# 1-Schematic_V1_0-A4988.net
KiCad netlist of a schematic drawn in EasyEDA
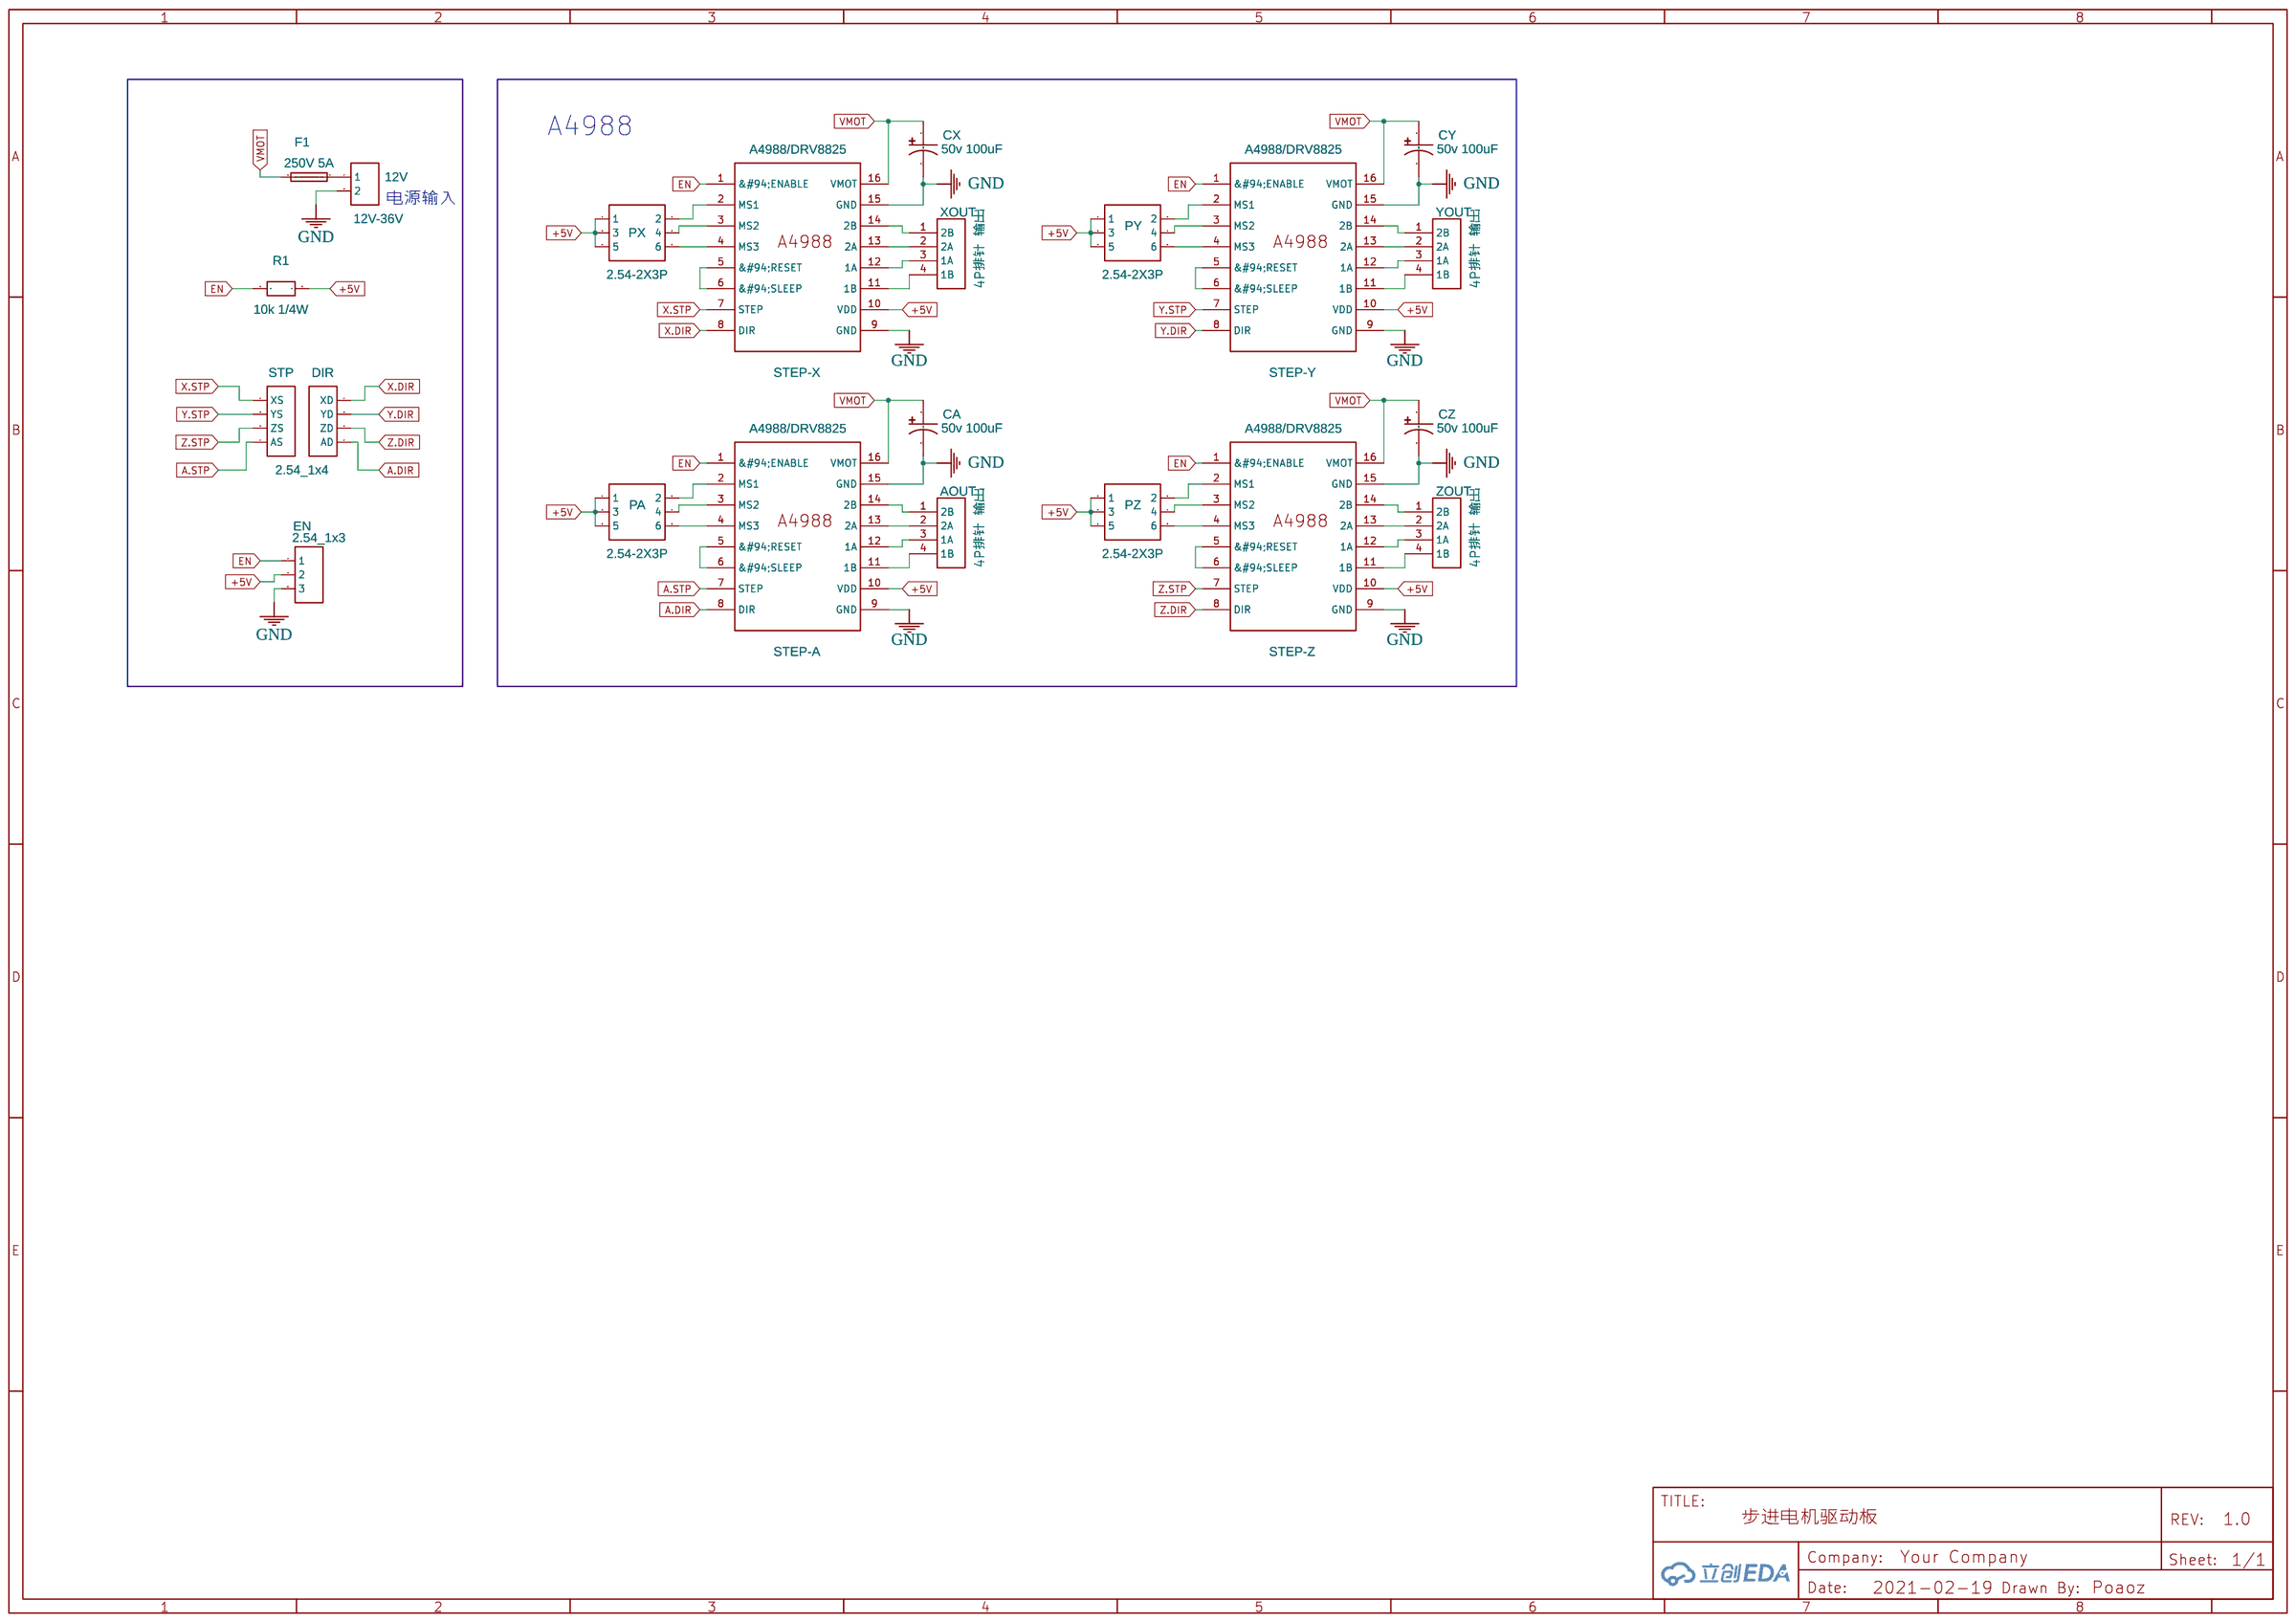
[diagram p0: schematic sheet]

(export (version "E")
  (design (tool "Eeschema 10.0.6"))
  (components
    (comp (ref "12V") (value "12V-36V") (libsource (lib "") (part "CONN-TH_2P-P5.00")))
    (comp (ref "AOUT") (value "4P排针 输出") (libsource (lib "") (part "4P排针_2")))
    (comp (ref "CA")
      (value "50v 100uF")
      (fields
        (field (name "BOM_Manufacturer Part") "NXA-50V100-8*11.5")
        (field (name "BOM_Supplier Part") "C165524")
      )
      (libsource (lib "") (part "NXA-50V100-8*11.5"))
    )
    (comp (ref "CX")
      (value "50v 100uF")
      (fields
        (field (name "BOM_Manufacturer Part") "NXA-50V100-8*11.5")
        (field (name "BOM_Supplier Part") "C165524")
      )
      (libsource (lib "") (part "NXA-50V100-8*11.5_2"))
    )
    (comp (ref "CY")
      (value "50v 100uF")
      (fields
        (field (name "BOM_Manufacturer Part") "NXA-50V100-8*11.5")
        (field (name "BOM_Supplier Part") "C165524")
      )
      (libsource (lib "") (part "NXA-50V100-8*11.5_1"))
    )
    (comp (ref "CZ")
      (value "50v 100uF")
      (fields
        (field (name "BOM_Manufacturer Part") "NXA-50V100-8*11.5")
        (field (name "BOM_Supplier Part") "C165524")
      )
      (libsource (lib "") (part "NXA-50V100-8*11.5_3"))
    )
    (comp (ref "DIR")
      (value "2.54_1x4")
      (fields (field (name "BOM_Supplier Part") "C225501"))
      (libsource (lib "") (part "HDR-F-2.54_1x4"))
    )
    (comp (ref "EN")
      (value "2.54_1x3")
      (fields (field (name "BOM_Supplier Part") "C146690"))
      (libsource (lib "") (part "HDR-F-2.54_1x3"))
    )
    (comp (ref "F1")
      (value "250V 5A")
      (fields
        (field (name "BOM_Manufacturer Part") "250V 5A Slow break")
        (field (name "BOM_Supplier Part") "C38454")
      )
      (libsource (lib "") (part "250V 5A Slow break"))
    )
    (comp (ref "PA")
      (value "2.54-2X3P")
      (fields
        (field (name "BOM_Manufacturer Part") "2X3 2.54mm IDC Box")
        (field (name "BOM_Supplier Part") "C11214")
      )
      (libsource (lib "") (part "HDR-IDC-2.54-2X3P_2"))
    )
    (comp (ref "PX")
      (value "2.54-2X3P")
      (fields
        (field (name "BOM_Manufacturer Part") "2X3 2.54mm IDC Box")
        (field (name "BOM_Supplier Part") "C11214")
      )
      (libsource (lib "") (part "HDR-IDC-2.54-2X3P_3"))
    )
    (comp (ref "PY")
      (value "2.54-2X3P")
      (fields
        (field (name "BOM_Manufacturer Part") "2X3 2.54mm IDC Box")
        (field (name "BOM_Supplier Part") "C11214")
      )
      (libsource (lib "") (part "HDR-IDC-2.54-2X3P_1"))
    )
    (comp (ref "PZ")
      (value "2.54-2X3P")
      (fields
        (field (name "BOM_Manufacturer Part") "2X3 2.54mm IDC Box")
        (field (name "BOM_Supplier Part") "C11214")
      )
      (libsource (lib "") (part "HDR-IDC-2.54-2X3P"))
    )
    (comp (ref "R1") (value "10k 1/4W") (libsource (lib "") (part "R_0603_EU")))
    (comp (ref "STEP-A") (value "A4988/DRV8825") (libsource (lib "") (part "A4988/DRV8825_2")))
    (comp (ref "STEP-X") (value "A4988/DRV8825") (libsource (lib "") (part "A4988/DRV8825")))
    (comp (ref "STEP-Y") (value "A4988/DRV8825") (libsource (lib "") (part "A4988/DRV8825_3")))
    (comp (ref "STEP-Z") (value "A4988/DRV8825") (libsource (lib "") (part "A4988/DRV8825_1")))
    (comp (ref "STP")
      (value "HDR-F-2.54_1x4")
      (fields (field (name "BOM_Supplier Part") "C225501"))
      (libsource (lib "") (part "HDR-F-2.54_1x4_1"))
    )
    (comp (ref "XOUT") (value "4P排针 输出") (libsource (lib "") (part "4P排针")))
    (comp (ref "YOUT") (value "4P排针 输出") (libsource (lib "") (part "4P排针_1")))
    (comp (ref "ZOUT") (value "4P排针 输出") (libsource (lib "") (part "4P排针_3")))
  )
  (nets
    (net (code "1") (name "+5V") (class "Default")
      (node (ref "EN") (pin "2") (pinfunction "2_2") (pintype "input"))
      (node (ref "PA") (pin "1") (pinfunction "1_1") (pintype "unspecified"))
      (node (ref "PA") (pin "3") (pinfunction "3_3") (pintype "unspecified"))
      (node (ref "PA") (pin "5") (pinfunction "5_5") (pintype "unspecified"))
      (node (ref "PX") (pin "1") (pinfunction "1_1") (pintype "unspecified"))
      (node (ref "PX") (pin "3") (pinfunction "3_3") (pintype "unspecified"))
      (node (ref "PX") (pin "5") (pinfunction "5_5") (pintype "unspecified"))
      (node (ref "PY") (pin "1") (pinfunction "1_1") (pintype "unspecified"))
      (node (ref "PY") (pin "3") (pinfunction "3_3") (pintype "unspecified"))
      (node (ref "PY") (pin "5") (pinfunction "5_5") (pintype "unspecified"))
      (node (ref "PZ") (pin "1") (pinfunction "1_1") (pintype "unspecified"))
      (node (ref "PZ") (pin "3") (pinfunction "3_3") (pintype "unspecified"))
      (node (ref "PZ") (pin "5") (pinfunction "5_5") (pintype "unspecified"))
      (node (ref "R1") (pin "2") (pinfunction "2_2") (pintype "unspecified"))
      (node (ref "STEP-A") (pin "10") (pinfunction "VDD_10") (pintype "unspecified"))
      (node (ref "STEP-X") (pin "10") (pinfunction "VDD_10") (pintype "unspecified"))
      (node (ref "STEP-Y") (pin "10") (pinfunction "VDD_10") (pintype "unspecified"))
      (node (ref "STEP-Z") (pin "10") (pinfunction "VDD_10") (pintype "unspecified"))
    )
    (net (code "2") (name "A.DIR") (class "Default")
      (node (ref "DIR") (pin "1") (pinfunction "AD_1") (pintype "unspecified"))
      (node (ref "STEP-A") (pin "8") (pinfunction "DIR_8") (pintype "unspecified"))
    )
    (net (code "3") (name "A.STP") (class "Default")
      (node (ref "STEP-A") (pin "7") (pinfunction "STEP_7") (pintype "unspecified"))
      (node (ref "STP") (pin "4") (pinfunction "AS_4") (pintype "unspecified"))
    )
    (net (code "4") (name "EN") (class "Default")
      (node (ref "EN") (pin "1") (pinfunction "1_1") (pintype "input"))
      (node (ref "R1") (pin "1") (pinfunction "1_1") (pintype "unspecified"))
      (node (ref "STEP-A") (pin "1") (pinfunction "&#94;ENABLE_1") (pintype "unspecified"))
      (node (ref "STEP-X") (pin "1") (pinfunction "&#94;ENABLE_1") (pintype "unspecified"))
      (node (ref "STEP-Y") (pin "1") (pinfunction "&#94;ENABLE_1") (pintype "unspecified"))
      (node (ref "STEP-Z") (pin "1") (pinfunction "&#94;ENABLE_1") (pintype "unspecified"))
    )
    (net (code "5") (name "GND") (class "Default")
      (node (ref "12V") (pin "2") (pinfunction "2_2") (pintype "unspecified"))
      (node (ref "CA") (pin "2") (pinfunction "2_2") (pintype "unspecified"))
      (node (ref "CX") (pin "2") (pinfunction "2_2") (pintype "unspecified"))
      (node (ref "CY") (pin "2") (pinfunction "2_2") (pintype "unspecified"))
      (node (ref "CZ") (pin "2") (pinfunction "2_2") (pintype "unspecified"))
      (node (ref "EN") (pin "3") (pinfunction "3_3") (pintype "input"))
      (node (ref "STEP-A") (pin "15") (pinfunction "GND_15") (pintype "unspecified"))
      (node (ref "STEP-A") (pin "9") (pinfunction "GND_9") (pintype "unspecified"))
      (node (ref "STEP-X") (pin "15") (pinfunction "GND_15") (pintype "unspecified"))
      (node (ref "STEP-X") (pin "9") (pinfunction "GND_9") (pintype "unspecified"))
      (node (ref "STEP-Y") (pin "15") (pinfunction "GND_15") (pintype "unspecified"))
      (node (ref "STEP-Y") (pin "9") (pinfunction "GND_9") (pintype "unspecified"))
      (node (ref "STEP-Z") (pin "15") (pinfunction "GND_15") (pintype "unspecified"))
      (node (ref "STEP-Z") (pin "9") (pinfunction "GND_9") (pintype "unspecified"))
    )
    (net (code "6") (name "Net-(12V-Pad1)") (class "Default")
      (node (ref "12V") (pin "1") (pinfunction "1_1") (pintype "unspecified"))
      (node (ref "F1") (pin "1") (pinfunction "1_1") (pintype "unspecified"))
    )
    (net (code "7") (name "Net-(AOUT-1A)") (class "Default")
      (node (ref "AOUT") (pin "3") (pinfunction "1A_3") (pintype "unspecified"))
      (node (ref "STEP-A") (pin "12") (pinfunction "1A_12") (pintype "unspecified"))
    )
    (net (code "8") (name "Net-(AOUT-1B)") (class "Default")
      (node (ref "AOUT") (pin "4") (pinfunction "1B_4") (pintype "unspecified"))
      (node (ref "STEP-A") (pin "11") (pinfunction "1B_11") (pintype "unspecified"))
    )
    (net (code "9") (name "Net-(AOUT-2A)") (class "Default")
      (node (ref "AOUT") (pin "2") (pinfunction "2A_2") (pintype "unspecified"))
      (node (ref "STEP-A") (pin "13") (pinfunction "2A_13") (pintype "unspecified"))
    )
    (net (code "10") (name "Net-(AOUT-2B)") (class "Default")
      (node (ref "AOUT") (pin "1") (pinfunction "2B_1") (pintype "unspecified"))
      (node (ref "STEP-A") (pin "14") (pinfunction "2B_14") (pintype "unspecified"))
    )
    (net (code "11") (name "Net-(STEP-A-&#94;RESET)") (class "Default")
      (node (ref "STEP-A") (pin "5") (pinfunction "&#94;RESET_5") (pintype "unspecified"))
      (node (ref "STEP-A") (pin "6") (pinfunction "&#94;SLEEP_6") (pintype "unspecified"))
    )
    (net (code "12") (name "Net-(STEP-A-MS1)") (class "Default")
      (node (ref "PA") (pin "2") (pinfunction "2_2") (pintype "unspecified"))
      (node (ref "STEP-A") (pin "2") (pinfunction "MS1_2") (pintype "unspecified"))
    )
    (net (code "13") (name "Net-(STEP-A-MS2)") (class "Default")
      (node (ref "PA") (pin "4") (pinfunction "4_4") (pintype "unspecified"))
      (node (ref "STEP-A") (pin "3") (pinfunction "MS2_3") (pintype "unspecified"))
    )
    (net (code "14") (name "Net-(STEP-A-MS3)") (class "Default")
      (node (ref "PA") (pin "6") (pinfunction "6_6") (pintype "unspecified"))
      (node (ref "STEP-A") (pin "4") (pinfunction "MS3_4") (pintype "unspecified"))
    )
    (net (code "15") (name "Net-(STEP-X-&#94;RESET)") (class "Default")
      (node (ref "STEP-X") (pin "5") (pinfunction "&#94;RESET_5") (pintype "unspecified"))
      (node (ref "STEP-X") (pin "6") (pinfunction "&#94;SLEEP_6") (pintype "unspecified"))
    )
    (net (code "16") (name "Net-(STEP-X-1A)") (class "Default")
      (node (ref "STEP-X") (pin "12") (pinfunction "1A_12") (pintype "unspecified"))
      (node (ref "XOUT") (pin "3") (pinfunction "1A_3") (pintype "unspecified"))
    )
    (net (code "17") (name "Net-(STEP-X-1B)") (class "Default")
      (node (ref "STEP-X") (pin "11") (pinfunction "1B_11") (pintype "unspecified"))
      (node (ref "XOUT") (pin "4") (pinfunction "1B_4") (pintype "unspecified"))
    )
    (net (code "18") (name "Net-(STEP-X-2A)") (class "Default")
      (node (ref "STEP-X") (pin "13") (pinfunction "2A_13") (pintype "unspecified"))
      (node (ref "XOUT") (pin "2") (pinfunction "2A_2") (pintype "unspecified"))
    )
    (net (code "19") (name "Net-(STEP-X-2B)") (class "Default")
      (node (ref "STEP-X") (pin "14") (pinfunction "2B_14") (pintype "unspecified"))
      (node (ref "XOUT") (pin "1") (pinfunction "2B_1") (pintype "unspecified"))
    )
    (net (code "20") (name "Net-(STEP-X-MS1)") (class "Default")
      (node (ref "PX") (pin "2") (pinfunction "2_2") (pintype "unspecified"))
      (node (ref "STEP-X") (pin "2") (pinfunction "MS1_2") (pintype "unspecified"))
    )
    (net (code "21") (name "Net-(STEP-X-MS2)") (class "Default")
      (node (ref "PX") (pin "4") (pinfunction "4_4") (pintype "unspecified"))
      (node (ref "STEP-X") (pin "3") (pinfunction "MS2_3") (pintype "unspecified"))
    )
    (net (code "22") (name "Net-(STEP-X-MS3)") (class "Default")
      (node (ref "PX") (pin "6") (pinfunction "6_6") (pintype "unspecified"))
      (node (ref "STEP-X") (pin "4") (pinfunction "MS3_4") (pintype "unspecified"))
    )
    (net (code "23") (name "Net-(STEP-Y-&#94;RESET)") (class "Default")
      (node (ref "STEP-Y") (pin "5") (pinfunction "&#94;RESET_5") (pintype "unspecified"))
      (node (ref "STEP-Y") (pin "6") (pinfunction "&#94;SLEEP_6") (pintype "unspecified"))
    )
    (net (code "24") (name "Net-(STEP-Y-1A)") (class "Default")
      (node (ref "STEP-Y") (pin "12") (pinfunction "1A_12") (pintype "unspecified"))
      (node (ref "YOUT") (pin "3") (pinfunction "1A_3") (pintype "unspecified"))
    )
    (net (code "25") (name "Net-(STEP-Y-1B)") (class "Default")
      (node (ref "STEP-Y") (pin "11") (pinfunction "1B_11") (pintype "unspecified"))
      (node (ref "YOUT") (pin "4") (pinfunction "1B_4") (pintype "unspecified"))
    )
    (net (code "26") (name "Net-(STEP-Y-2A)") (class "Default")
      (node (ref "STEP-Y") (pin "13") (pinfunction "2A_13") (pintype "unspecified"))
      (node (ref "YOUT") (pin "2") (pinfunction "2A_2") (pintype "unspecified"))
    )
    (net (code "27") (name "Net-(STEP-Y-2B)") (class "Default")
      (node (ref "STEP-Y") (pin "14") (pinfunction "2B_14") (pintype "unspecified"))
      (node (ref "YOUT") (pin "1") (pinfunction "2B_1") (pintype "unspecified"))
    )
    (net (code "28") (name "Net-(STEP-Y-MS1)") (class "Default")
      (node (ref "PY") (pin "2") (pinfunction "2_2") (pintype "unspecified"))
      (node (ref "STEP-Y") (pin "2") (pinfunction "MS1_2") (pintype "unspecified"))
    )
    (net (code "29") (name "Net-(STEP-Y-MS2)") (class "Default")
      (node (ref "PY") (pin "4") (pinfunction "4_4") (pintype "unspecified"))
      (node (ref "STEP-Y") (pin "3") (pinfunction "MS2_3") (pintype "unspecified"))
    )
    (net (code "30") (name "Net-(STEP-Y-MS3)") (class "Default")
      (node (ref "PY") (pin "6") (pinfunction "6_6") (pintype "unspecified"))
      (node (ref "STEP-Y") (pin "4") (pinfunction "MS3_4") (pintype "unspecified"))
    )
    (net (code "31") (name "Net-(STEP-Z-&#94;RESET)") (class "Default")
      (node (ref "STEP-Z") (pin "5") (pinfunction "&#94;RESET_5") (pintype "unspecified"))
      (node (ref "STEP-Z") (pin "6") (pinfunction "&#94;SLEEP_6") (pintype "unspecified"))
    )
    (net (code "32") (name "Net-(STEP-Z-1A)") (class "Default")
      (node (ref "STEP-Z") (pin "12") (pinfunction "1A_12") (pintype "unspecified"))
      (node (ref "ZOUT") (pin "3") (pinfunction "1A_3") (pintype "unspecified"))
    )
    (net (code "33") (name "Net-(STEP-Z-1B)") (class "Default")
      (node (ref "STEP-Z") (pin "11") (pinfunction "1B_11") (pintype "unspecified"))
      (node (ref "ZOUT") (pin "4") (pinfunction "1B_4") (pintype "unspecified"))
    )
    (net (code "34") (name "Net-(STEP-Z-2A)") (class "Default")
      (node (ref "STEP-Z") (pin "13") (pinfunction "2A_13") (pintype "unspecified"))
      (node (ref "ZOUT") (pin "2") (pinfunction "2A_2") (pintype "unspecified"))
    )
    (net (code "35") (name "Net-(STEP-Z-2B)") (class "Default")
      (node (ref "STEP-Z") (pin "14") (pinfunction "2B_14") (pintype "unspecified"))
      (node (ref "ZOUT") (pin "1") (pinfunction "2B_1") (pintype "unspecified"))
    )
    (net (code "36") (name "Net-(STEP-Z-MS1)") (class "Default")
      (node (ref "PZ") (pin "2") (pinfunction "2_2") (pintype "unspecified"))
      (node (ref "STEP-Z") (pin "2") (pinfunction "MS1_2") (pintype "unspecified"))
    )
    (net (code "37") (name "Net-(STEP-Z-MS2)") (class "Default")
      (node (ref "PZ") (pin "4") (pinfunction "4_4") (pintype "unspecified"))
      (node (ref "STEP-Z") (pin "3") (pinfunction "MS2_3") (pintype "unspecified"))
    )
    (net (code "38") (name "Net-(STEP-Z-MS3)") (class "Default")
      (node (ref "PZ") (pin "6") (pinfunction "6_6") (pintype "unspecified"))
      (node (ref "STEP-Z") (pin "4") (pinfunction "MS3_4") (pintype "unspecified"))
    )
    (net (code "39") (name "VMOT") (class "Default")
      (node (ref "CA") (pin "1") (pinfunction "1_1") (pintype "unspecified"))
      (node (ref "CX") (pin "1") (pinfunction "1_1") (pintype "unspecified"))
      (node (ref "CY") (pin "1") (pinfunction "1_1") (pintype "unspecified"))
      (node (ref "CZ") (pin "1") (pinfunction "1_1") (pintype "unspecified"))
      (node (ref "F1") (pin "2") (pinfunction "2_2") (pintype "unspecified"))
      (node (ref "STEP-A") (pin "16") (pinfunction "VMOT_16") (pintype "unspecified"))
      (node (ref "STEP-X") (pin "16") (pinfunction "VMOT_16") (pintype "unspecified"))
      (node (ref "STEP-Y") (pin "16") (pinfunction "VMOT_16") (pintype "unspecified"))
      (node (ref "STEP-Z") (pin "16") (pinfunction "VMOT_16") (pintype "unspecified"))
    )
    (net (code "40") (name "X.DIR") (class "Default")
      (node (ref "DIR") (pin "4") (pinfunction "XD_4") (pintype "unspecified"))
      (node (ref "STEP-X") (pin "8") (pinfunction "DIR_8") (pintype "unspecified"))
    )
    (net (code "41") (name "X.STP") (class "Default")
      (node (ref "STEP-X") (pin "7") (pinfunction "STEP_7") (pintype "unspecified"))
      (node (ref "STP") (pin "1") (pinfunction "XS_1") (pintype "unspecified"))
    )
    (net (code "42") (name "Y.DIR") (class "Default")
      (node (ref "DIR") (pin "3") (pinfunction "YD_3") (pintype "unspecified"))
      (node (ref "STEP-Y") (pin "8") (pinfunction "DIR_8") (pintype "unspecified"))
    )
    (net (code "43") (name "Y.STP") (class "Default")
      (node (ref "STEP-Y") (pin "7") (pinfunction "STEP_7") (pintype "unspecified"))
      (node (ref "STP") (pin "2") (pinfunction "YS_2") (pintype "unspecified"))
    )
    (net (code "44") (name "Z.DIR") (class "Default")
      (node (ref "DIR") (pin "2") (pinfunction "ZD_2") (pintype "unspecified"))
      (node (ref "STEP-Z") (pin "8") (pinfunction "DIR_8") (pintype "unspecified"))
    )
    (net (code "45") (name "Z.STP") (class "Default")
      (node (ref "STEP-Z") (pin "7") (pinfunction "STEP_7") (pintype "unspecified"))
      (node (ref "STP") (pin "3") (pinfunction "ZS_3") (pintype "unspecified"))
    )
  )
)
